# OBI_SlaveBoard_rev1.net
KiCad netlist of a schematic drawn in EAGLE
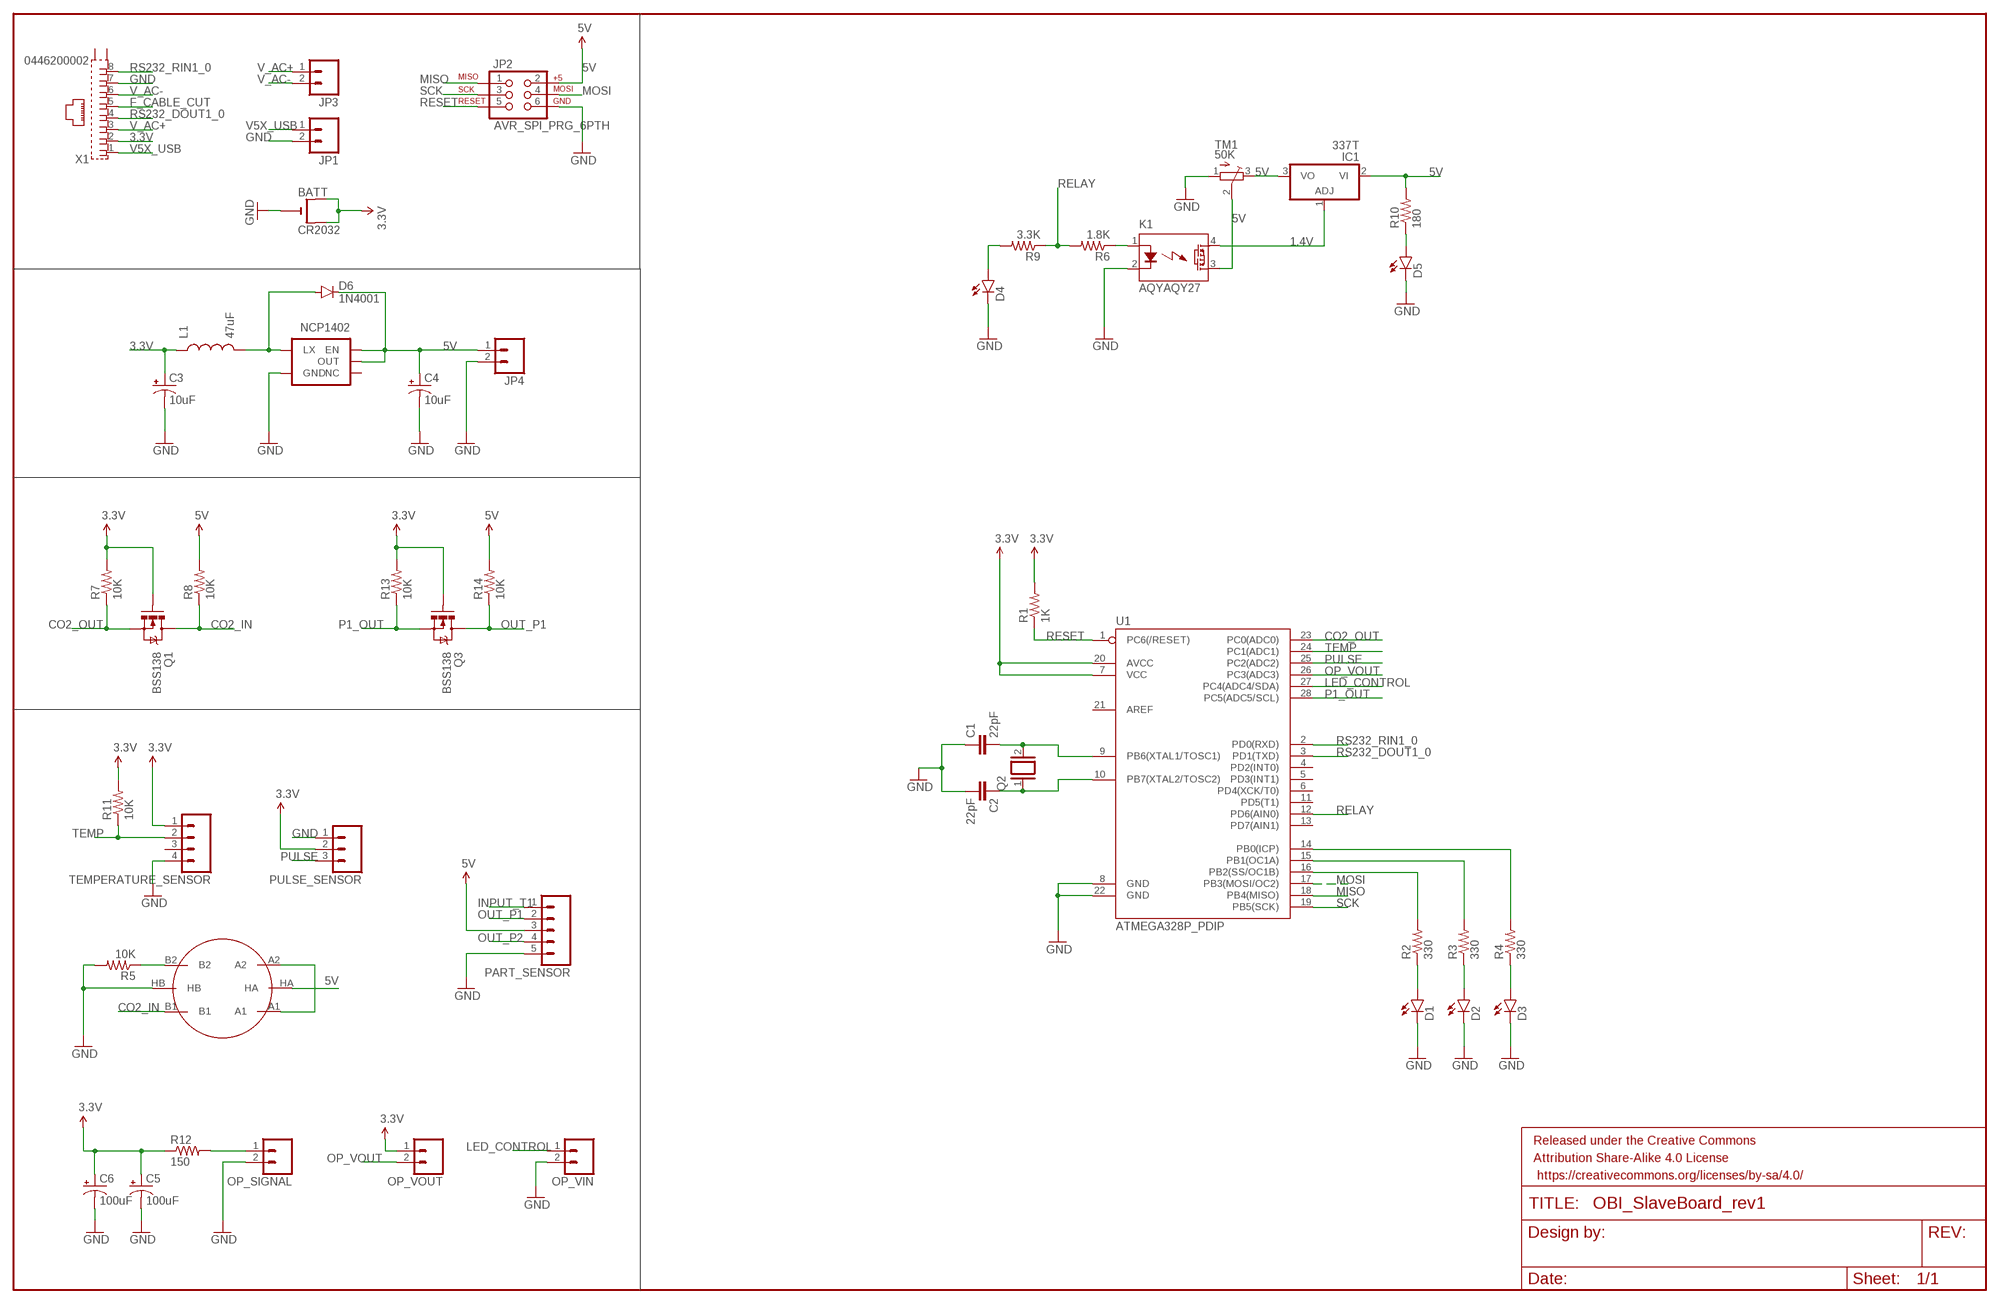
[diagram p0: schematic, sheet 1]

(export (version "E")
  (design (tool "Eeschema 10.0.6"))
  (components
    (comp (ref "BATT")
      (value "CR2032")
      (footprint "eagle-import:CR2032-THRU")
      (libsource (lib "eagle-import") (part "CR2032THM"))
    )
    (comp (ref "C1")
      (value "22pF")
      (footprint "eagle-import:CAP-PTH-SMALL-KIT")
      (libsource (lib "eagle-import") (part "CAPKIT"))
    )
    (comp (ref "C2")
      (value "22pF")
      (footprint "eagle-import:CAP-PTH-SMALL-KIT")
      (libsource (lib "eagle-import") (part "CAPKIT"))
    )
    (comp (ref "C3")
      (value "10uF")
      (footprint "eagle-import:CPOL-RADIAL-10UF-25V")
      (libsource (lib "eagle-import") (part "CAP_POLPTH2"))
    )
    (comp (ref "C4")
      (value "10uF")
      (footprint "eagle-import:CPOL-RADIAL-10UF-25V")
      (libsource (lib "eagle-import") (part "CAP_POLPTH2"))
    )
    (comp (ref "C5")
      (value "100uF")
      (footprint "eagle-import:CPOL-RADIAL-10UF-25V")
      (libsource (lib "eagle-import") (part "CAP_POLPTH2"))
    )
    (comp (ref "C6")
      (value "100uF")
      (footprint "eagle-import:CPOL-RADIAL-10UF-25V")
      (libsource (lib "eagle-import") (part "CAP_POLPTH2"))
    )
    (comp (ref "CO2_SENSOR")
      (value "METHANE_SENSOR")
      (footprint "eagle-import:MQ-3")
      (libsource (lib "eagle-import") (part "METHANE_SENSOR"))
    )
    (comp (ref "D1")
      (value "LED5MM")
      (footprint "eagle-import:LED5MM")
      (libsource (lib "eagle-import") (part "LED5MM"))
    )
    (comp (ref "D2")
      (value "LED5MM")
      (footprint "eagle-import:LED5MM")
      (libsource (lib "eagle-import") (part "LED5MM"))
    )
    (comp (ref "D3")
      (value "LED5MM")
      (footprint "eagle-import:LED5MM")
      (libsource (lib "eagle-import") (part "LED5MM"))
    )
    (comp (ref "D4")
      (value "LED5MM")
      (footprint "eagle-import:LED5MM")
      (libsource (lib "eagle-import") (part "LED5MM"))
    )
    (comp (ref "D5")
      (value "LED5MM")
      (footprint "eagle-import:LED5MM")
      (libsource (lib "eagle-import") (part "LED5MM"))
    )
    (comp (ref "D6")
      (value "1N4001")
      (footprint "eagle-import:DIODE-1N4001")
      (libsource (lib "eagle-import") (part "DIODEPTH"))
    )
    (comp (ref "FRAME1")
      (value "FRAME-LEDGER")
      (footprint "eagle-import:CREATIVE_COMMONS")
      (libsource (lib "eagle-import") (part "FRAME-LEDGER"))
    )
    (comp (ref "IC1")
      (value "337T")
      (footprint "eagle-import:TO220H")
      (libsource (lib "eagle-import") (part "337T"))
    )
    (comp (ref "JP1")
      (value "M023.5MM")
      (footprint "eagle-import:SCREWTERMINAL-3.5MM-2")
      (libsource (lib "eagle-import") (part "M023.5MM"))
    )
    (comp (ref "JP2")
      (value "AVR_SPI_PRG_6PTH")
      (footprint "eagle-import:2X3")
      (libsource (lib "eagle-import") (part "AVR_SPI_PRG_6PTH"))
    )
    (comp (ref "JP3")
      (value "M023.5MM")
      (footprint "eagle-import:SCREWTERMINAL-3.5MM-2")
      (libsource (lib "eagle-import") (part "M023.5MM"))
    )
    (comp (ref "JP4")
      (value "M023.5MM")
      (footprint "eagle-import:SCREWTERMINAL-3.5MM-2")
      (libsource (lib "eagle-import") (part "M023.5MM"))
    )
    (comp (ref "K1")
      (value "AQYAQY27")
      (footprint "eagle-import:AQY27")
      (libsource (lib "eagle-import") (part "AQYAQY27"))
    )
    (comp (ref "L1")
      (value "47uF")
      (footprint "eagle-import:CR54")
      (libsource (lib "eagle-import") (part "INDUCTORCR54"))
    )
    (comp (ref "NCP1402")
      (value "V_REG_NCP1400SOT23-5")
      (footprint "eagle-import:SOT23-5")
      (libsource (lib "eagle-import") (part "V_REG_NCP1400SOT23-5"))
    )
    (comp (ref "OP_SIGNAL")
      (value "M023.5MM")
      (footprint "eagle-import:SCREWTERMINAL-3.5MM-2")
      (libsource (lib "eagle-import") (part "M023.5MM"))
    )
    (comp (ref "OP_VIN")
      (value "M023.5MM")
      (footprint "eagle-import:SCREWTERMINAL-3.5MM-2")
      (libsource (lib "eagle-import") (part "M023.5MM"))
    )
    (comp (ref "OP_VOUT")
      (value "M023.5MM")
      (footprint "eagle-import:SCREWTERMINAL-3.5MM-2")
      (libsource (lib "eagle-import") (part "M023.5MM"))
    )
    (comp (ref "PART_SENSOR")
      (value "M05JST")
      (footprint "eagle-import:JST-5-PTH")
      (libsource (lib "eagle-import") (part "M05JST"))
    )
    (comp (ref "PULSE_SENSOR")
      (value "M03-SCREW-5MM")
      (footprint "eagle-import:SCREWTERMINAL-5MM-3")
      (libsource (lib "eagle-import") (part "M03-SCREW-5MM"))
    )
    (comp (ref "Q1")
      (value "BSS138")
      (footprint "eagle-import:TO-92")
      (libsource (lib "eagle-import") (part "MOSFET-NCHANNEL2N7000"))
    )
    (comp (ref "Q2")
      (value "XTAL/S")
      (footprint "eagle-import:QS")
      (libsource (lib "eagle-import") (part "XTAL/S"))
    )
    (comp (ref "Q3")
      (value "BSS138")
      (footprint "eagle-import:TO-92")
      (libsource (lib "eagle-import") (part "MOSFET-NCHANNEL2N7000"))
    )
    (comp (ref "R1")
      (value "1K")
      (footprint "eagle-import:AXIAL-0.4")
      (libsource (lib "eagle-import") (part "RESISTORPTH-1/4W"))
    )
    (comp (ref "R2")
      (value "330")
      (footprint "eagle-import:AXIAL-0.4")
      (libsource (lib "eagle-import") (part "SparkFun-Resistors_RESISTORPTH-1/4W"))
    )
    (comp (ref "R3")
      (value "330")
      (footprint "eagle-import:AXIAL-0.4")
      (libsource (lib "eagle-import") (part "SparkFun-Resistors_RESISTORPTH-1/4W"))
    )
    (comp (ref "R4")
      (value "330")
      (footprint "eagle-import:AXIAL-0.4")
      (libsource (lib "eagle-import") (part "SparkFun-Resistors_RESISTORPTH-1/4W"))
    )
    (comp (ref "R5")
      (value "10K")
      (footprint "eagle-import:AXIAL-0.4")
      (libsource (lib "eagle-import") (part "RESISTORPTH-1/4W"))
    )
    (comp (ref "R6")
      (value "1.8K")
      (footprint "eagle-import:AXIAL-0.4")
      (libsource (lib "eagle-import") (part "RESISTORPTH-1/4W"))
    )
    (comp (ref "R7")
      (value "10K")
      (footprint "eagle-import:AXIAL-0.4")
      (libsource (lib "eagle-import") (part "RESISTORPTH-1/4W"))
    )
    (comp (ref "R8")
      (value "10K")
      (footprint "eagle-import:AXIAL-0.4")
      (libsource (lib "eagle-import") (part "RESISTORPTH-1/4W"))
    )
    (comp (ref "R9")
      (value "3.3K")
      (footprint "eagle-import:AXIAL-0.4")
      (libsource (lib "eagle-import") (part "RESISTORPTH-1/4W"))
    )
    (comp (ref "R10")
      (value "180")
      (footprint "eagle-import:AXIAL-0.4")
      (libsource (lib "eagle-import") (part "SparkFun-Resistors_RESISTORPTH-1/4W"))
    )
    (comp (ref "R11")
      (value "10K")
      (footprint "eagle-import:AXIAL-0.4")
      (libsource (lib "eagle-import") (part "SparkFun-Resistors_RESISTORPTH-1/4W"))
    )
    (comp (ref "R12")
      (value "150")
      (footprint "eagle-import:AXIAL-0.4")
      (libsource (lib "eagle-import") (part "SparkFun-Resistors_RESISTORPTH-1/4W"))
    )
    (comp (ref "R13")
      (value "10K")
      (footprint "eagle-import:AXIAL-0.4")
      (libsource (lib "eagle-import") (part "RESISTORPTH-1/4W"))
    )
    (comp (ref "R14")
      (value "10K")
      (footprint "eagle-import:AXIAL-0.4")
      (libsource (lib "eagle-import") (part "RESISTORPTH-1/4W"))
    )
    (comp (ref "TEMPERATURE_SENSOR")
      (value "M04SCREW")
      (footprint "eagle-import:SCREWTERMINAL-3.5MM-4")
      (libsource (lib "eagle-import") (part "M04SCREW"))
    )
    (comp (ref "TM1")
      (value "50K")
      (footprint "eagle-import:TC33X")
      (libsource (lib "eagle-import") (part "TRIMPOTTC33X"))
    )
    (comp (ref "U1")
      (value "ATMEGA328P_PDIP")
      (footprint "eagle-import:DIL28-3")
      (libsource (lib "eagle-import") (part "ATMEGA328P_PDIP"))
    )
    (comp (ref "X1")
      (value "0446200002")
      (footprint "eagle-import:0446200002")
      (fields (field (name "MF") "MOLEX"))
      (libsource (lib "eagle-import") (part "0446200002"))
    )
  )
  (nets
    (net (code "1") (name "/1.4V") (class "Default")
      (node (ref "IC1") (pin "1") (pinfunction "ADJ_1") (pintype "input"))
      (node (ref "K1") (pin "4") (pinfunction "DS1_4") (pintype "passive"))
    )
    (net (code "2") (name "/CO2_IN") (class "Default")
      (node (ref "CO2_SENSOR") (pin "B1") (pinfunction "B1_B1") (pintype "bidirectional"))
      (node (ref "Q1") (pin "3") (pinfunction "D_3") (pintype "passive"))
      (node (ref "R8") (pin "P$1") (pinfunction "1_P$1") (pintype "passive"))
    )
    (net (code "3") (name "/CO2_OUT") (class "Default")
      (node (ref "Q1") (pin "1") (pinfunction "S_1") (pintype "passive"))
      (node (ref "R7") (pin "P$1") (pinfunction "1_P$1") (pintype "passive"))
      (node (ref "U1") (pin "23") (pinfunction "PC0(ADC0)_23") (pintype "bidirectional"))
    )
    (net (code "4") (name "/F_CABLE_CUT") (class "Default")
      (node (ref "X1") (pin "5") (pinfunction "5_5") (pintype "passive"))
    )
    (net (code "5") (name "/INPUT_T1") (class "Default")
      (node (ref "PART_SENSOR") (pin "1") (pinfunction "1_1") (pintype "passive"))
    )
    (net (code "6") (name "/LED_CONTROL") (class "Default")
      (node (ref "OP_VIN") (pin "1") (pinfunction "1_1") (pintype "passive"))
      (node (ref "U1") (pin "27") (pinfunction "PC4(ADC4/SDA)_27") (pintype "bidirectional"))
    )
    (net (code "7") (name "/MISO") (class "Default")
      (node (ref "JP2") (pin "1") (pinfunction "1_1") (pintype "passive"))
      (node (ref "U1") (pin "18") (pinfunction "PB4(MISO)_18") (pintype "bidirectional"))
    )
    (net (code "8") (name "/MOSI") (class "Default")
      (node (ref "JP2") (pin "4") (pinfunction "4_4") (pintype "passive"))
      (node (ref "U1") (pin "17") (pinfunction "PB3(MOSI/OC2)_17") (pintype "bidirectional"))
    )
    (net (code "9") (name "/OP_VOUT") (class "Default")
      (node (ref "OP_VOUT") (pin "2") (pinfunction "2_2") (pintype "passive"))
      (node (ref "U1") (pin "26") (pinfunction "PC3(ADC3)_26") (pintype "bidirectional"))
    )
    (net (code "10") (name "/OUT_P1") (class "Default")
      (node (ref "PART_SENSOR") (pin "2") (pinfunction "2_2") (pintype "passive"))
      (node (ref "Q3") (pin "3") (pinfunction "D_3") (pintype "passive"))
      (node (ref "R14") (pin "P$1") (pinfunction "1_P$1") (pintype "passive"))
    )
    (net (code "11") (name "/OUT_P2") (class "Default")
      (node (ref "PART_SENSOR") (pin "4") (pinfunction "4_4") (pintype "passive"))
    )
    (net (code "12") (name "/P1_OUT") (class "Default")
      (node (ref "Q3") (pin "1") (pinfunction "S_1") (pintype "passive"))
      (node (ref "R13") (pin "P$1") (pinfunction "1_P$1") (pintype "passive"))
      (node (ref "U1") (pin "28") (pinfunction "PC5(ADC5/SCL)_28") (pintype "bidirectional"))
    )
    (net (code "13") (name "/PULSE") (class "Default")
      (node (ref "PULSE_SENSOR") (pin "3") (pinfunction "3_3") (pintype "passive"))
      (node (ref "U1") (pin "25") (pinfunction "PC2(ADC2)_25") (pintype "bidirectional"))
    )
    (net (code "14") (name "/RELAY") (class "Default")
      (node (ref "R6") (pin "P$2") (pinfunction "2_P$2") (pintype "passive"))
      (node (ref "R9") (pin "P$1") (pinfunction "1_P$1") (pintype "passive"))
      (node (ref "U1") (pin "12") (pinfunction "PD6(AIN0)_12") (pintype "bidirectional"))
    )
    (net (code "15") (name "/RESET") (class "Default")
      (node (ref "JP2") (pin "5") (pinfunction "5_5") (pintype "passive"))
      (node (ref "R1") (pin "P$1") (pinfunction "1_P$1") (pintype "passive"))
      (node (ref "U1") (pin "1") (pinfunction "PC6(/RESET)_1") (pintype "bidirectional"))
    )
    (net (code "16") (name "/RS232_DOUT1_0") (class "Default")
      (node (ref "U1") (pin "3") (pinfunction "PD1(TXD)_3") (pintype "bidirectional"))
      (node (ref "X1") (pin "4") (pinfunction "4_4") (pintype "passive"))
    )
    (net (code "17") (name "/RS232_RIN1_0") (class "Default")
      (node (ref "U1") (pin "2") (pinfunction "PD0(RXD)_2") (pintype "bidirectional"))
      (node (ref "X1") (pin "8") (pinfunction "8_8") (pintype "passive"))
    )
    (net (code "18") (name "/SCK") (class "Default")
      (node (ref "JP2") (pin "3") (pinfunction "3_3") (pintype "passive"))
      (node (ref "U1") (pin "19") (pinfunction "PB5(SCK)_19") (pintype "bidirectional"))
    )
    (net (code "19") (name "/TEMP") (class "Default")
      (node (ref "R11") (pin "P$1") (pinfunction "1_P$1") (pintype "passive"))
      (node (ref "TEMPERATURE_SENSOR") (pin "2") (pinfunction "2_2") (pintype "passive"))
      (node (ref "U1") (pin "24") (pinfunction "PC1(ADC1)_24") (pintype "bidirectional"))
    )
    (net (code "20") (name "/V5X_USB") (class "Default")
      (node (ref "JP1") (pin "1") (pinfunction "1_1") (pintype "passive"))
      (node (ref "X1") (pin "1") (pinfunction "1_1") (pintype "passive"))
    )
    (net (code "21") (name "/V_AC+") (class "Default")
      (node (ref "JP3") (pin "1") (pinfunction "1_1") (pintype "passive"))
      (node (ref "X1") (pin "3") (pinfunction "3_3") (pintype "passive"))
    )
    (net (code "22") (name "/V_AC-") (class "Default")
      (node (ref "JP3") (pin "2") (pinfunction "2_2") (pintype "passive"))
      (node (ref "X1") (pin "6") (pinfunction "6_6") (pintype "passive"))
    )
    (net (code "23") (name "3.3V") (class "Default")
      (node (ref "BATT") (pin "+1") (pinfunction "+_+1") (pintype "passive"))
      (node (ref "BATT") (pin "+2") (pinfunction "+1_+2") (pintype "passive"))
      (node (ref "C3") (pin "1") (pinfunction "+_1") (pintype "passive"))
      (node (ref "C5") (pin "1") (pinfunction "+_1") (pintype "passive"))
      (node (ref "C6") (pin "1") (pinfunction "+_1") (pintype "passive"))
      (node (ref "L1") (pin "P$1") (pinfunction "1_P$1") (pintype "passive"))
      (node (ref "OP_VOUT") (pin "1") (pinfunction "1_1") (pintype "passive"))
      (node (ref "PULSE_SENSOR") (pin "2") (pinfunction "2_2") (pintype "passive"))
      (node (ref "Q1") (pin "2") (pinfunction "G_2") (pintype "passive"))
      (node (ref "Q3") (pin "2") (pinfunction "G_2") (pintype "passive"))
      (node (ref "R1") (pin "P$2") (pinfunction "2_P$2") (pintype "passive"))
      (node (ref "R11") (pin "P$2") (pinfunction "2_P$2") (pintype "passive"))
      (node (ref "R12") (pin "P$1") (pinfunction "1_P$1") (pintype "passive"))
      (node (ref "R13") (pin "P$2") (pinfunction "2_P$2") (pintype "passive"))
      (node (ref "R7") (pin "P$2") (pinfunction "2_P$2") (pintype "passive"))
      (node (ref "TEMPERATURE_SENSOR") (pin "1") (pinfunction "1_1") (pintype "passive"))
      (node (ref "U1") (pin "20") (pinfunction "AVCC_20") (pintype "bidirectional"))
      (node (ref "U1") (pin "7") (pinfunction "VCC_7") (pintype "bidirectional"))
      (node (ref "X1") (pin "2") (pinfunction "2_2") (pintype "passive"))
    )
    (net (code "24") (name "5V") (class "Default")
      (node (ref "C4") (pin "1") (pinfunction "+_1") (pintype "passive"))
      (node (ref "CO2_SENSOR") (pin "HA") (pinfunction "HA_HA") (pintype "bidirectional"))
      (node (ref "D6") (pin "C") (pinfunction "C_C") (pintype "passive"))
      (node (ref "IC1") (pin "2") (pinfunction "VI_2") (pintype "input"))
      (node (ref "IC1") (pin "3") (pinfunction "VO_3") (pintype "passive"))
      (node (ref "JP2") (pin "2") (pinfunction "2_2") (pintype "passive"))
      (node (ref "JP4") (pin "1") (pinfunction "1_1") (pintype "passive"))
      (node (ref "K1") (pin "3") (pinfunction "DS2_3") (pintype "passive"))
      (node (ref "NCP1402") (pin "1") (pinfunction "EN_1") (pintype "input"))
      (node (ref "NCP1402") (pin "2") (pinfunction "OUT_2") (pintype "passive"))
      (node (ref "PART_SENSOR") (pin "3") (pinfunction "3_3") (pintype "passive"))
      (node (ref "R10") (pin "P$2") (pinfunction "2_P$2") (pintype "passive"))
      (node (ref "R14") (pin "P$2") (pinfunction "2_P$2") (pintype "passive"))
      (node (ref "R8") (pin "P$2") (pinfunction "2_P$2") (pintype "passive"))
      (node (ref "TM1") (pin "2") (pinfunction "S_2") (pintype "passive"))
      (node (ref "TM1") (pin "3") (pinfunction "E_3") (pintype "passive"))
    )
    (net (code "25") (name "GND") (class "Default")
      (node (ref "BATT") (pin "-") (pinfunction "-_-") (pintype "passive"))
      (node (ref "C1") (pin "1") (pinfunction "1_1") (pintype "passive"))
      (node (ref "C2") (pin "2") (pinfunction "2_2") (pintype "passive"))
      (node (ref "C3") (pin "2") (pinfunction "-_2") (pintype "passive"))
      (node (ref "C4") (pin "2") (pinfunction "-_2") (pintype "passive"))
      (node (ref "C5") (pin "2") (pinfunction "-_2") (pintype "passive"))
      (node (ref "C6") (pin "2") (pinfunction "-_2") (pintype "passive"))
      (node (ref "CO2_SENSOR") (pin "HB") (pinfunction "HB_HB") (pintype "bidirectional"))
      (node (ref "D1") (pin "K") (pinfunction "C_K") (pintype "passive"))
      (node (ref "D2") (pin "K") (pinfunction "C_K") (pintype "passive"))
      (node (ref "D3") (pin "K") (pinfunction "C_K") (pintype "passive"))
      (node (ref "D4") (pin "K") (pinfunction "C_K") (pintype "passive"))
      (node (ref "D5") (pin "K") (pinfunction "C_K") (pintype "passive"))
      (node (ref "JP1") (pin "2") (pinfunction "2_2") (pintype "passive"))
      (node (ref "JP2") (pin "6") (pinfunction "6_6") (pintype "passive"))
      (node (ref "JP4") (pin "2") (pinfunction "2_2") (pintype "passive"))
      (node (ref "K1") (pin "2") (pinfunction "K_2") (pintype "passive"))
      (node (ref "NCP1402") (pin "4") (pinfunction "GND_4") (pintype "input"))
      (node (ref "OP_SIGNAL") (pin "2") (pinfunction "2_2") (pintype "passive"))
      (node (ref "OP_VIN") (pin "2") (pinfunction "2_2") (pintype "passive"))
      (node (ref "PART_SENSOR") (pin "5") (pinfunction "5_5") (pintype "passive"))
      (node (ref "PULSE_SENSOR") (pin "1") (pinfunction "1_1") (pintype "passive"))
      (node (ref "R5") (pin "P$2") (pinfunction "2_P$2") (pintype "passive"))
      (node (ref "TEMPERATURE_SENSOR") (pin "4") (pinfunction "4_4") (pintype "passive"))
      (node (ref "TM1") (pin "1") (pinfunction "A_1") (pintype "passive"))
      (node (ref "U1") (pin "22") (pinfunction "GND_22") (pintype "bidirectional"))
      (node (ref "U1") (pin "8") (pinfunction "GND_8") (pintype "bidirectional"))
      (node (ref "X1") (pin "7") (pinfunction "7_7") (pintype "passive"))
    )
    (net (code "26") (name "Net-(CO2_SENSOR-PadA1)") (class "Default")
      (node (ref "CO2_SENSOR") (pin "A1") (pinfunction "A1_A1") (pintype "bidirectional"))
      (node (ref "CO2_SENSOR") (pin "A2") (pinfunction "A2_A2") (pintype "bidirectional"))
    )
    (net (code "27") (name "Net-(K1-A)") (class "Default")
      (node (ref "K1") (pin "1") (pinfunction "A_1") (pintype "passive"))
      (node (ref "R6") (pin "P$1") (pinfunction "1_P$1") (pintype "passive"))
    )
    (net (code "28") (name "Net-(L1-2)") (class "Default")
      (node (ref "D6") (pin "A") (pinfunction "A_A") (pintype "passive"))
      (node (ref "L1") (pin "P$2") (pinfunction "2_P$2") (pintype "passive"))
      (node (ref "NCP1402") (pin "5") (pinfunction "LX_5") (pintype "input"))
    )
    (net (code "29") (name "Net-(R2-1)") (class "Default")
      (node (ref "D1") (pin "A") (pinfunction "A_A") (pintype "passive"))
      (node (ref "R2") (pin "P$1") (pinfunction "1_P$1") (pintype "passive"))
    )
    (net (code "30") (name "Net-(R2-2)") (class "Default")
      (node (ref "R2") (pin "P$2") (pinfunction "2_P$2") (pintype "passive"))
      (node (ref "U1") (pin "16") (pinfunction "PB2(SS/OC1B)_16") (pintype "bidirectional"))
    )
    (net (code "31") (name "Net-(R3-1)") (class "Default")
      (node (ref "D2") (pin "A") (pinfunction "A_A") (pintype "passive"))
      (node (ref "R3") (pin "P$1") (pinfunction "1_P$1") (pintype "passive"))
    )
    (net (code "32") (name "Net-(R3-2)") (class "Default")
      (node (ref "R3") (pin "P$2") (pinfunction "2_P$2") (pintype "passive"))
      (node (ref "U1") (pin "15") (pinfunction "PB1(OC1A)_15") (pintype "bidirectional"))
    )
    (net (code "33") (name "Net-(R4-1)") (class "Default")
      (node (ref "D3") (pin "A") (pinfunction "A_A") (pintype "passive"))
      (node (ref "R4") (pin "P$1") (pinfunction "1_P$1") (pintype "passive"))
    )
    (net (code "34") (name "Net-(R4-2)") (class "Default")
      (node (ref "R4") (pin "P$2") (pinfunction "2_P$2") (pintype "passive"))
      (node (ref "U1") (pin "14") (pinfunction "PB0(ICP)_14") (pintype "bidirectional"))
    )
    (net (code "35") (name "Net-(R5-1)") (class "Default")
      (node (ref "CO2_SENSOR") (pin "B2") (pinfunction "B2_B2") (pintype "bidirectional"))
      (node (ref "R5") (pin "P$1") (pinfunction "1_P$1") (pintype "passive"))
    )
    (net (code "36") (name "Net-(R9-2)") (class "Default")
      (node (ref "D4") (pin "A") (pinfunction "A_A") (pintype "passive"))
      (node (ref "R9") (pin "P$2") (pinfunction "2_P$2") (pintype "passive"))
    )
    (net (code "37") (name "Net-(R10-1)") (class "Default")
      (node (ref "D5") (pin "A") (pinfunction "A_A") (pintype "passive"))
      (node (ref "R10") (pin "P$1") (pinfunction "1_P$1") (pintype "passive"))
    )
    (net (code "38") (name "Net-(R12-2)") (class "Default")
      (node (ref "OP_SIGNAL") (pin "1") (pinfunction "1_1") (pintype "passive"))
      (node (ref "R12") (pin "P$2") (pinfunction "2_P$2") (pintype "passive"))
    )
    (net (code "39") (name "Net-(U1-PB6(XTAL1{slash}TOSC1))") (class "Default")
      (node (ref "C1") (pin "2") (pinfunction "2_2") (pintype "passive"))
      (node (ref "Q2") (pin "2") (pinfunction "2_2") (pintype "passive"))
      (node (ref "U1") (pin "9") (pinfunction "PB6(XTAL1/TOSC1)_9") (pintype "bidirectional"))
    )
    (net (code "40") (name "Net-(U1-PB7(XTAL2{slash}TOSC2))") (class "Default")
      (node (ref "C2") (pin "1") (pinfunction "1_1") (pintype "passive"))
      (node (ref "Q2") (pin "1") (pinfunction "1_1") (pintype "passive"))
      (node (ref "U1") (pin "10") (pinfunction "PB7(XTAL2/TOSC2)_10") (pintype "bidirectional"))
    )
    (net (code "41") (name "unconnected-(NCP1402-NC-Pad3)") (class "Default")
      (node (ref "NCP1402") (pin "3") (pinfunction "NC_3") (pintype "input"))
    )
    (net (code "42") (name "unconnected-(TEMPERATURE_SENSOR-Pad3)") (class "Default")
      (node (ref "TEMPERATURE_SENSOR") (pin "3") (pinfunction "3_3") (pintype "passive"))
    )
    (net (code "43") (name "unconnected-(U1-AREF-Pad21)") (class "Default")
      (node (ref "U1") (pin "21") (pinfunction "AREF_21") (pintype "bidirectional"))
    )
    (net (code "44") (name "unconnected-(U1-PD2(INT0)-Pad4)") (class "Default")
      (node (ref "U1") (pin "4") (pinfunction "PD2(INT0)_4") (pintype "bidirectional"))
    )
    (net (code "45") (name "unconnected-(U1-PD3(INT1)-Pad5)") (class "Default")
      (node (ref "U1") (pin "5") (pinfunction "PD3(INT1)_5") (pintype "bidirectional"))
    )
    (net (code "46") (name "unconnected-(U1-PD4(XCK{slash}T0)-Pad6)") (class "Default")
      (node (ref "U1") (pin "6") (pinfunction "PD4(XCK/T0)_6") (pintype "bidirectional"))
    )
    (net (code "47") (name "unconnected-(U1-PD5(T1)-Pad11)") (class "Default")
      (node (ref "U1") (pin "11") (pinfunction "PD5(T1)_11") (pintype "bidirectional"))
    )
    (net (code "48") (name "unconnected-(U1-PD7(AIN1)-Pad13)") (class "Default")
      (node (ref "U1") (pin "13") (pinfunction "PD7(AIN1)_13") (pintype "bidirectional"))
    )
    (net (code "49") (name "unconnected-(X1-S1-PadS@1)") (class "Default")
      (node (ref "X1") (pin "S@1") (pinfunction "S1_S@1") (pintype "passive"))
    )
    (net (code "50") (name "unconnected-(X1-S2-PadS@2)") (class "Default")
      (node (ref "X1") (pin "S@2") (pinfunction "S2_S@2") (pintype "passive"))
    )
  )
)
